# RS232_2xNPN_FTDI.net
KiCad netlist of a schematic drawn in EAGLE
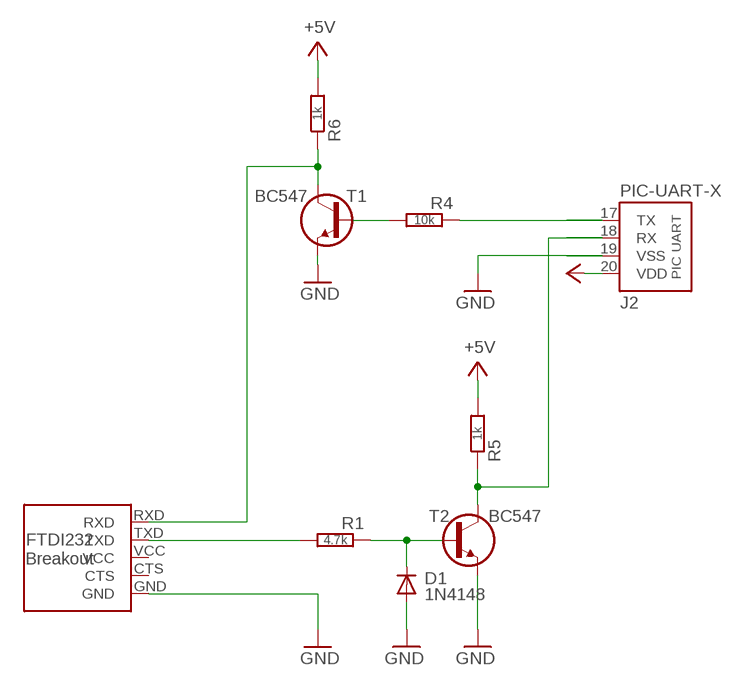
[diagram p0: schematic, sheet 1]

(export (version "E")
  (design (tool "Eeschema 10.0.6"))
  (components
    (comp (ref "D1")
      (value "1N4148")
      (footprint "eagle-import:DO34-5V")
      (libsource (lib "eagle-import") (part "1N414834-5V"))
    )
    (comp (ref "J1")
      (value "FTDI232-BO-5P-L")
      (footprint "eagle-import:FTDI232-BO-5-L")
      (libsource (lib "eagle-import") (part "FTDI232-BO-5P-L"))
    )
    (comp (ref "J2")
      (value "PIC-UART-X")
      (footprint "eagle-import:PIC-UART-X")
      (libsource (lib "eagle-import") (part "PIC-UART-X"))
    )
    (comp (ref "R1")
      (value "4.7k")
      (footprint "eagle-import:0202_7")
      (libsource (lib "eagle-import") (part "R0202/7"))
    )
    (comp (ref "R4")
      (value "10k")
      (footprint "eagle-import:0202_7")
      (libsource (lib "eagle-import") (part "R0202/7"))
    )
    (comp (ref "R5")
      (value "1k")
      (footprint "eagle-import:0202_7-V")
      (libsource (lib "eagle-import") (part "R0202/7-V"))
    )
    (comp (ref "R6")
      (value "1k")
      (footprint "eagle-import:0202_7-V")
      (libsource (lib "eagle-import") (part "R0202/7-V"))
    )
    (comp (ref "T1")
      (value "BC547")
      (footprint "eagle-import:TO92-CBE")
      (libsource (lib "eagle-import") (part "BC547CBE"))
    )
    (comp (ref "T2")
      (value "BC547")
      (footprint "eagle-import:TO92-CBE")
      (libsource (lib "eagle-import") (part "BC547CBE"))
    )
  )
  (nets
    (net (code "1") (name "+5V") (class "Default")
      (node (ref "J2") (pin "20") (pinfunction "VDD_20") (pintype "passive"))
      (node (ref "R5") (pin "2") (pinfunction "2_2") (pintype "passive"))
      (node (ref "R6") (pin "2") (pinfunction "2_2") (pintype "passive"))
    )
    (net (code "2") (name "GND") (class "Default")
      (node (ref "D1") (pin "A") (pinfunction "A_A") (pintype "passive"))
      (node (ref "J1") (pin "GND") (pinfunction "GND_GND") (pintype "bidirectional"))
      (node (ref "J2") (pin "19") (pinfunction "VSS_19") (pintype "passive"))
      (node (ref "T1") (pin "E") (pinfunction "E_E") (pintype "passive"))
      (node (ref "T2") (pin "E") (pinfunction "E_E") (pintype "passive"))
    )
    (net (code "3") (name "Net-(D1-PadC)") (class "Default")
      (node (ref "D1") (pin "C") (pinfunction "C_C") (pintype "passive"))
      (node (ref "R1") (pin "1") (pinfunction "1_1") (pintype "passive"))
      (node (ref "T2") (pin "B") (pinfunction "B_B") (pintype "passive"))
    )
    (net (code "4") (name "Net-(J1-PadRXD)") (class "Default")
      (node (ref "J1") (pin "RXD") (pinfunction "RXD_RXD") (pintype "bidirectional"))
      (node (ref "R6") (pin "1") (pinfunction "1_1") (pintype "passive"))
      (node (ref "T1") (pin "C") (pinfunction "C_C") (pintype "passive"))
    )
    (net (code "5") (name "Net-(J1-PadTXD)") (class "Default")
      (node (ref "J1") (pin "TXD") (pinfunction "TXD_TXD") (pintype "bidirectional"))
      (node (ref "R1") (pin "2") (pinfunction "2_2") (pintype "passive"))
    )
    (net (code "6") (name "Net-(J2-RX)") (class "Default")
      (node (ref "J2") (pin "18") (pinfunction "RX_18") (pintype "passive"))
      (node (ref "R5") (pin "1") (pinfunction "1_1") (pintype "passive"))
      (node (ref "T2") (pin "C") (pinfunction "C_C") (pintype "passive"))
    )
    (net (code "7") (name "Net-(J2-TX)") (class "Default")
      (node (ref "J2") (pin "17") (pinfunction "TX_17") (pintype "passive"))
      (node (ref "R4") (pin "1") (pinfunction "1_1") (pintype "passive"))
    )
    (net (code "8") (name "Net-(R4-Pad2)") (class "Default")
      (node (ref "R4") (pin "2") (pinfunction "2_2") (pintype "passive"))
      (node (ref "T1") (pin "B") (pinfunction "B_B") (pintype "passive"))
    )
    (net (code "9") (name "unconnected-(J1-PadCTS)") (class "Default")
      (node (ref "J1") (pin "CTS") (pinfunction "CTS_CTS") (pintype "bidirectional"))
    )
    (net (code "10") (name "unconnected-(J1-PadVCC)") (class "Default")
      (node (ref "J1") (pin "VCC") (pinfunction "VCC_VCC") (pintype "bidirectional"))
    )
  )
)
